# 2.net
KiCad netlist of a schematic drawn in Altium Designer
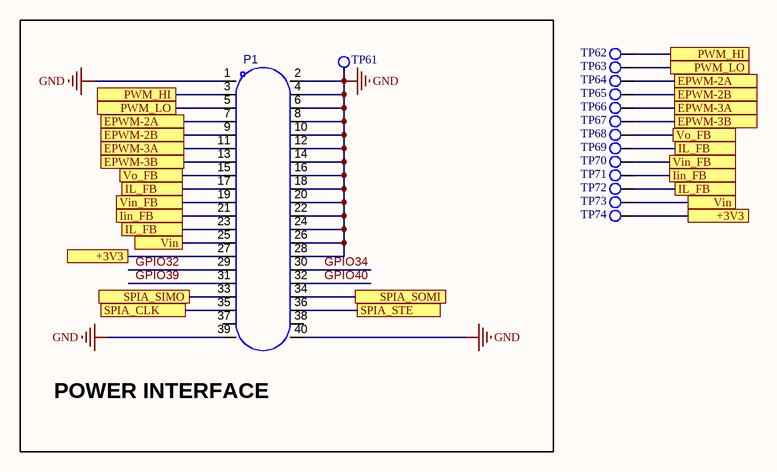
[diagram p0: 2.SchDoc]

(export (version "E")
  (design (tool "Eeschema 10.0.6"))
  (components
    (comp (ref "P1")
      (value "zx-pm2.54-2-20py")
      (footprint "HDR-TH_40P-P2.54-V-F-R2-C20-S2.54")
      (fields
        (field (name "MANUFACTURER") "Megastar(兆星)")
        (field (name "MANUFACTURERPART") "ZX-PM2.54-2-20PY")
      )
      (libsource (lib "60W-PD-V2") (part "zx-pm2.54-2-20py"))
    )
    (comp (ref "TP61")
      (value "TP-pad0.8")
      (footprint "PAD0.8/1.6")
      (libsource (lib "60W-PD-V2") (part "TP-pad0.8"))
    )
    (comp (ref "TP62")
      (value "TP-pad0.8")
      (footprint "PAD0.8/1.6")
      (libsource (lib "60W-PD-V2") (part "TP-pad0.8"))
    )
    (comp (ref "TP63")
      (value "TP-pad0.8")
      (footprint "PAD0.8/1.6")
      (libsource (lib "60W-PD-V2") (part "TP-pad0.8"))
    )
    (comp (ref "TP64")
      (value "TP-pad0.8")
      (footprint "PAD0.8/1.6")
      (libsource (lib "60W-PD-V2") (part "TP-pad0.8"))
    )
    (comp (ref "TP65")
      (value "TP-pad0.8")
      (footprint "PAD0.8/1.6")
      (libsource (lib "60W-PD-V2") (part "TP-pad0.8"))
    )
    (comp (ref "TP66")
      (value "TP-pad0.8")
      (footprint "PAD0.8/1.6")
      (libsource (lib "60W-PD-V2") (part "TP-pad0.8"))
    )
    (comp (ref "TP67")
      (value "TP-pad0.8")
      (footprint "PAD0.8/1.6")
      (libsource (lib "60W-PD-V2") (part "TP-pad0.8"))
    )
    (comp (ref "TP68")
      (value "TEST POINT")
      (footprint "TP-1.5")
      (libsource (lib "60W-PD") (part "TEST POINT"))
    )
    (comp (ref "TP69")
      (value "TEST POINT")
      (footprint "TP-1.5")
      (libsource (lib "60W-PD") (part "TEST POINT"))
    )
    (comp (ref "TP70")
      (value "TEST POINT")
      (footprint "TP-1.5")
      (libsource (lib "60W-PD") (part "TEST POINT"))
    )
    (comp (ref "TP71")
      (value "TEST POINT")
      (footprint "TP-1.5")
      (libsource (lib "60W-PD") (part "TEST POINT"))
    )
    (comp (ref "TP72")
      (value "TEST POINT")
      (footprint "TP-1.5")
      (libsource (lib "60W-PD") (part "TEST POINT"))
    )
    (comp (ref "TP73")
      (value "TEST POINT")
      (footprint "TP-1.5")
      (libsource (lib "60W-PD") (part "TEST POINT"))
    )
    (comp (ref "TP74")
      (value "TEST POINT")
      (footprint "TP-1.5")
      (libsource (lib "60W-PD") (part "TEST POINT"))
    )
  )
  (nets
    (net (code "1") (name "/+3V3") (class "Default")
      (node (ref "P1") (pin "27") (pinfunction "27_27") (pintype "passive"))
      (node (ref "TP74") (pin "1") (pinfunction "1_1") (pintype "passive"))
    )
    (net (code "2") (name "/EPWM-2A") (class "Default")
      (node (ref "P1") (pin "7") (pinfunction "7_7") (pintype "passive"))
      (node (ref "TP64") (pin "1") (pinfunction "1_1") (pintype "passive"))
    )
    (net (code "3") (name "/EPWM-2B") (class "Default")
      (node (ref "P1") (pin "9") (pinfunction "9_9") (pintype "passive"))
      (node (ref "TP65") (pin "1") (pinfunction "1_1") (pintype "passive"))
    )
    (net (code "4") (name "/EPWM-3A") (class "Default")
      (node (ref "P1") (pin "11") (pinfunction "11_11") (pintype "passive"))
      (node (ref "TP66") (pin "1") (pinfunction "1_1") (pintype "passive"))
    )
    (net (code "5") (name "/EPWM-3B") (class "Default")
      (node (ref "P1") (pin "13") (pinfunction "13_13") (pintype "passive"))
      (node (ref "TP67") (pin "1") (pinfunction "1_1") (pintype "passive"))
    )
    (net (code "6") (name "/GPIO32") (class "Default")
      (node (ref "P1") (pin "29") (pinfunction "29_29") (pintype "passive"))
    )
    (net (code "7") (name "/GPIO34") (class "Default")
      (node (ref "P1") (pin "30") (pinfunction "30_30") (pintype "passive"))
    )
    (net (code "8") (name "/GPIO39") (class "Default")
      (node (ref "P1") (pin "31") (pinfunction "31_31") (pintype "passive"))
    )
    (net (code "9") (name "/GPIO40") (class "Default")
      (node (ref "P1") (pin "32") (pinfunction "32_32") (pintype "passive"))
    )
    (net (code "10") (name "/IL_FB") (class "Default")
      (node (ref "P1") (pin "17") (pinfunction "17_17") (pintype "passive"))
      (node (ref "P1") (pin "23") (pinfunction "23_23") (pintype "passive"))
      (node (ref "TP69") (pin "1") (pinfunction "1_1") (pintype "passive"))
      (node (ref "TP72") (pin "1") (pinfunction "1_1") (pintype "passive"))
    )
    (net (code "11") (name "/Iin_FB") (class "Default")
      (node (ref "P1") (pin "21") (pinfunction "21_21") (pintype "passive"))
      (node (ref "TP71") (pin "1") (pinfunction "1_1") (pintype "passive"))
    )
    (net (code "12") (name "/PWM_HI") (class "Default")
      (node (ref "P1") (pin "3") (pinfunction "3_3") (pintype "passive"))
      (node (ref "TP62") (pin "1") (pinfunction "1_1") (pintype "passive"))
    )
    (net (code "13") (name "/PWM_LO") (class "Default")
      (node (ref "P1") (pin "5") (pinfunction "5_5") (pintype "passive"))
      (node (ref "TP63") (pin "1") (pinfunction "1_1") (pintype "passive"))
    )
    (net (code "14") (name "/SPIA_CLK") (class "Default")
      (node (ref "P1") (pin "35") (pinfunction "35_35") (pintype "passive"))
    )
    (net (code "15") (name "/SPIA_SIMO") (class "Default")
      (node (ref "P1") (pin "33") (pinfunction "33_33") (pintype "passive"))
    )
    (net (code "16") (name "/SPIA_SOMI") (class "Default")
      (node (ref "P1") (pin "34") (pinfunction "34_34") (pintype "passive"))
    )
    (net (code "17") (name "/SPIA_STE") (class "Default")
      (node (ref "P1") (pin "36") (pinfunction "36_36") (pintype "passive"))
    )
    (net (code "18") (name "/Vin") (class "Default")
      (node (ref "P1") (pin "25") (pinfunction "25_25") (pintype "passive"))
      (node (ref "TP73") (pin "1") (pinfunction "1_1") (pintype "passive"))
    )
    (net (code "19") (name "/Vin_FB") (class "Default")
      (node (ref "P1") (pin "19") (pinfunction "19_19") (pintype "passive"))
      (node (ref "TP70") (pin "1") (pinfunction "1_1") (pintype "passive"))
    )
    (net (code "20") (name "/Vo_FB") (class "Default")
      (node (ref "P1") (pin "15") (pinfunction "15_15") (pintype "passive"))
      (node (ref "TP68") (pin "1") (pinfunction "1_1") (pintype "passive"))
    )
    (net (code "21") (name "GND") (class "Default")
      (node (ref "P1") (pin "1") (pinfunction "1_1") (pintype "passive"))
      (node (ref "P1") (pin "10") (pinfunction "10_10") (pintype "passive"))
      (node (ref "P1") (pin "12") (pinfunction "12_12") (pintype "passive"))
      (node (ref "P1") (pin "14") (pinfunction "14_14") (pintype "passive"))
      (node (ref "P1") (pin "16") (pinfunction "16_16") (pintype "passive"))
      (node (ref "P1") (pin "18") (pinfunction "18_18") (pintype "passive"))
      (node (ref "P1") (pin "2") (pinfunction "2_2") (pintype "passive"))
      (node (ref "P1") (pin "20") (pinfunction "20_20") (pintype "passive"))
      (node (ref "P1") (pin "22") (pinfunction "22_22") (pintype "passive"))
      (node (ref "P1") (pin "24") (pinfunction "24_24") (pintype "passive"))
      (node (ref "P1") (pin "26") (pinfunction "26_26") (pintype "passive"))
      (node (ref "P1") (pin "28") (pinfunction "28_28") (pintype "passive"))
      (node (ref "P1") (pin "39") (pinfunction "39_39") (pintype "passive"))
      (node (ref "P1") (pin "4") (pinfunction "4_4") (pintype "passive"))
      (node (ref "P1") (pin "40") (pinfunction "40_40") (pintype "passive"))
      (node (ref "P1") (pin "6") (pinfunction "6_6") (pintype "passive"))
      (node (ref "P1") (pin "8") (pinfunction "8_8") (pintype "passive"))
      (node (ref "TP61") (pin "1") (pinfunction "1_1") (pintype "passive"))
    )
    (net (code "22") (name "unconnected-(P1-Pad37)") (class "Default")
      (node (ref "P1") (pin "37") (pinfunction "37_37") (pintype "passive"))
    )
    (net (code "23") (name "unconnected-(P1-Pad38)") (class "Default")
      (node (ref "P1") (pin "38") (pinfunction "38_38") (pintype "passive"))
    )
  )
)
